# Microcontroller.net
KiCad netlist of a schematic drawn in Altium Designer
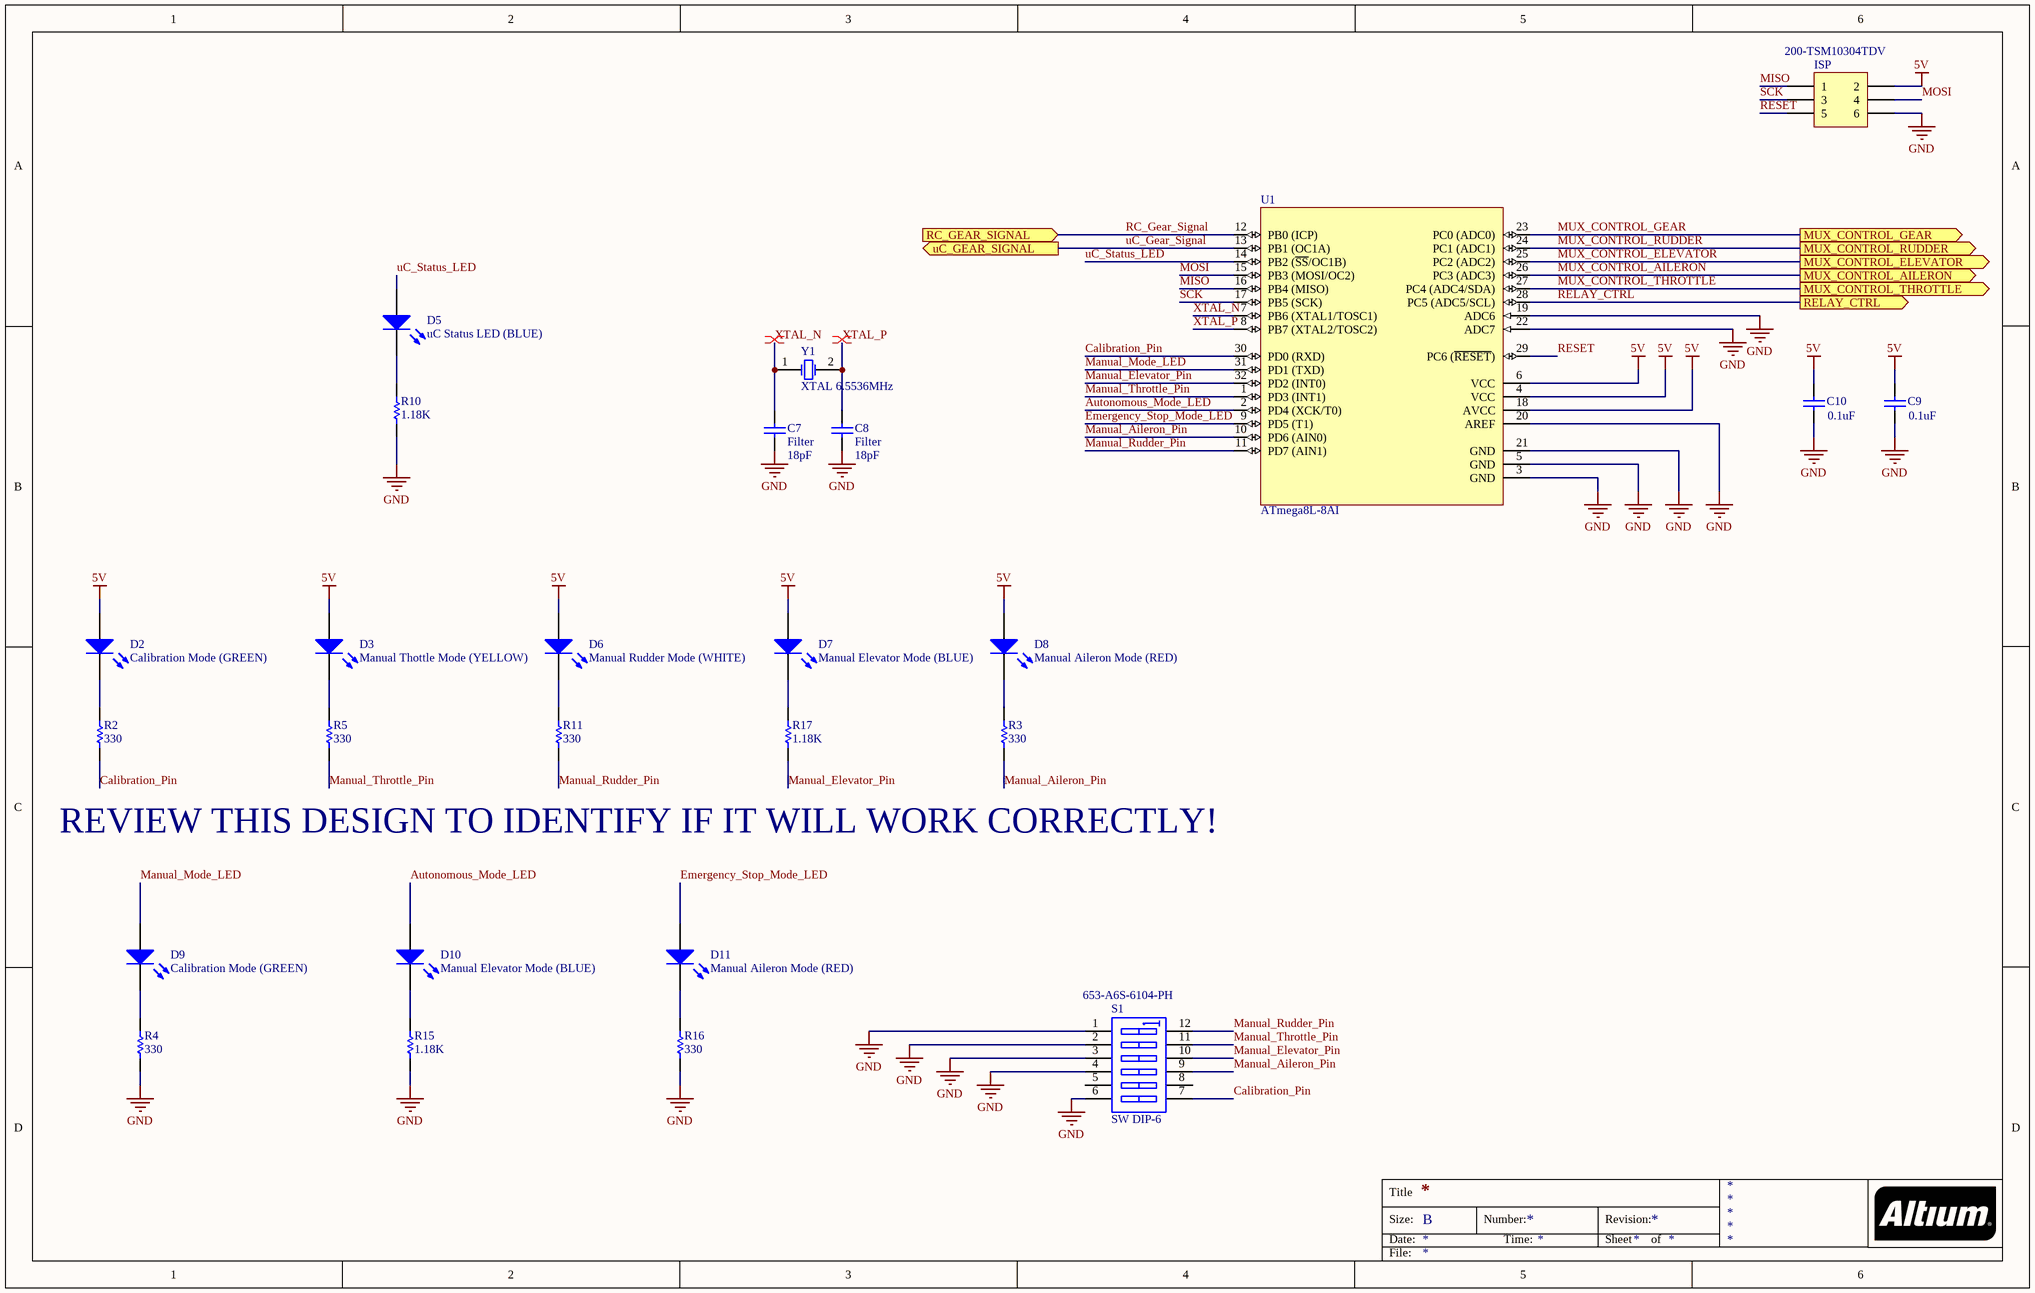
[diagram p0: Microcontroller.SchDoc]

(export (version "E")
  (design (tool "Eeschema 10.0.6"))
  (components
    (comp (ref "C7")
      (value "Filter")
      (footprint "1608[0603]")
      (description "Capacitor")
      (fields
        (field (name "ALTIUM_VALUE") "18pF")
        (field (name "MANUFACTURER") "KEMET")
        (field (name "TOLERANCE") "1%")
        (field (name "PUBLISHER") "Altium Limited")
      )
      (libsource (lib "Miscellaneous Devices") (part "Cap"))
    )
    (comp (ref "C8")
      (value "Filter")
      (footprint "1608[0603]")
      (description "Capacitor")
      (fields
        (field (name "ALTIUM_VALUE") "18pF")
        (field (name "MANUFACTURER") "KEMET")
        (field (name "TOLERANCE") "1%")
        (field (name "PUBLISHER") "Altium Limited")
      )
      (libsource (lib "Miscellaneous Devices") (part "Cap"))
    )
    (comp (ref "C9")
      (value "0.1uF")
      (footprint "1608[0603]")
      (description "Multilayer Ceramic Capacitors MLCC - SMD/SMT 0603 .1uF 50volts X7R 10%")
      (fields
        (field (name "MANUFACTURER PART NUMBER") "VJ0603Y104KXAAC")
        (field (name "MANUFACTURER") "Vishay Semiconductors")
      )
      (libsource (lib "Miscellaneous Devices") (part "Cap"))
    )
    (comp (ref "C10")
      (value "0.1uF")
      (footprint "1608[0603]")
      (description "Multilayer Ceramic Capacitors MLCC - SMD/SMT 0603 .1uF 50volts X7R 10%")
      (fields
        (field (name "MANUFACTURER PART NUMBER") "VJ0603Y104KXAAC")
        (field (name "MANUFACTURER") "Vishay Semiconductors")
      )
      (libsource (lib "Miscellaneous Devices") (part "Cap"))
    )
    (comp (ref "D2")
      (value "Calibration Mode (GREEN)")
      (footprint "1608[0603]")
      (description "Standard LEDs - SMD Ultra Green, 574nm 2.2V, 45mcd")
      (fields
        (field (name "MANUFACTURER") "Lumex")
        (field (name "MANUFACTURER PART NUMBER") "SML-LX0603SUGW-TR")
      )
      (libsource (lib "Miscellaneous Devices") (part "LED0"))
    )
    (comp (ref "D3")
      (value "Manual Thottle Mode (YELLOW)")
      (footprint "1608[0603]")
      (description "Standard LEDs - SMD Yellow 589nm 22mcd 5mA")
      (fields
        (field (name "MANUFACTURER PART NUMBER") "LTST-C193KSKT-5A")
        (field (name "MANUFACTURER") "Vishay Lite-On")
      )
      (libsource (lib "Miscellaneous Devices") (part "LED0"))
    )
    (comp (ref "D5")
      (value "uC Status LED (BLUE)")
      (footprint "1608[0603]")
      (description "Standard LEDs - SMD 0603 Dome Lens LED Blue- 470nm")
      (fields
        (field (name "MANUFACTURER PART NUMBER") "APHD1608LVBC/D")
        (field (name "MANUFACTURER") "Kingbright")
      )
      (libsource (lib "Miscellaneous Devices") (part "LED0"))
    )
    (comp (ref "D6")
      (value "Manual Rudder Mode (WHITE)")
      (footprint "1608[0603]")
      (description "Standard LEDs - SMD CHIPLED, WHITE")
      (fields
        (field (name "MANUFACTURER") "Osram Opto")
        (field (name "MANUFACTURER PART NUMBER") "Q65110-A7209")
      )
      (libsource (lib "Miscellaneous Devices") (part "LED0"))
    )
    (comp (ref "D7")
      (value "Manual Elevator Mode (BLUE)")
      (footprint "1608[0603]")
      (description "Standard LEDs - SMD 0603 Dome Lens LED Blue- 470nm")
      (fields
        (field (name "MANUFACTURER PART NUMBER") "APHD1608LVBC/D")
        (field (name "MANUFACTURER") "Kingbright")
      )
      (libsource (lib "Miscellaneous Devices") (part "LED0"))
    )
    (comp (ref "D8")
      (value "Manual Aileron Mode (RED)")
      (footprint "1608[0603]")
      (description "Standard LEDs - SMD Super Red, 660nm 1.7V, 45mcd")
      (fields
        (field (name "MANUFACTURER PART NUMBER") "SML-LX0603SRW-TR")
        (field (name "MANUFACTURER") "Lumex")
      )
      (libsource (lib "Miscellaneous Devices") (part "LED0"))
    )
    (comp (ref "D9")
      (value "Calibration Mode (GREEN)")
      (footprint "1608[0603]")
      (description "Standard LEDs - SMD Ultra Green, 574nm 2.2V, 45mcd")
      (fields
        (field (name "MANUFACTURER") "Lumex")
        (field (name "MANUFACTURER PART NUMBER") "SML-LX0603SUGW-TR")
      )
      (libsource (lib "Miscellaneous Devices") (part "LED0"))
    )
    (comp (ref "D10")
      (value "Manual Elevator Mode (BLUE)")
      (footprint "1608[0603]")
      (description "Standard LEDs - SMD 0603 Dome Lens LED Blue- 470nm")
      (fields
        (field (name "MANUFACTURER PART NUMBER") "APHD1608LVBC/D")
        (field (name "MANUFACTURER") "Kingbright")
      )
      (libsource (lib "Miscellaneous Devices") (part "LED0"))
    )
    (comp (ref "D11")
      (value "Manual Aileron Mode (RED)")
      (footprint "1608[0603]")
      (description "Standard LEDs - SMD Super Red, 660nm 1.7V, 45mcd")
      (fields
        (field (name "MANUFACTURER PART NUMBER") "SML-LX0603SRW-TR")
        (field (name "MANUFACTURER") "Lumex")
      )
      (libsource (lib "Miscellaneous Devices") (part "LED0"))
    )
    (comp (ref "ISP")
      (value "Header 3X2")
      (footprint "HDR2X3")
      (description "Header, 3-Pin, Dual row")
      (fields
        (field (name "SUPPLIER PART NUMBER 1") "200-TSM10304TDV")
        (field (name "MANUFACTURER") "Samtec")
        (field (name "MANUFACTURER PART NUMBER") "TSM-103-04-T-DV")
        (field (name "PUBLISHER") "Altium Limited")
      )
      (libsource (lib "Miscellaneous Connectors") (part "Header 3X2"))
    )
    (comp (ref "R2")
      (value "330")
      (footprint "1608[0603]")
      (description "Thick Film Resistors - SMD 330 ohm 0.5% 0.33W AEC-Q200")
      (fields
        (field (name "MANUFACTURER") "KOA Speer")
        (field (name "MANUFACTURER PART NUMBER") "SG73G1JTTD3300D")
      )
      (libsource (lib "Miscellaneous Devices") (part "Res1"))
    )
    (comp (ref "R3")
      (value "330")
      (footprint "1608[0603]")
      (description "Thick Film Resistors - SMD 330 ohm 0.5% 0.33W AEC-Q200")
      (fields
        (field (name "MANUFACTURER") "KOA Speer")
        (field (name "MANUFACTURER PART NUMBER") "SG73G1JTTD3300D")
      )
      (libsource (lib "Miscellaneous Devices") (part "Res1"))
    )
    (comp (ref "R4")
      (value "330")
      (footprint "1608[0603]")
      (description "Thick Film Resistors - SMD 330 ohm 0.5% 0.33W AEC-Q200")
      (fields
        (field (name "MANUFACTURER") "KOA Speer")
        (field (name "MANUFACTURER PART NUMBER") "SG73G1JTTD3300D")
      )
      (libsource (lib "Miscellaneous Devices") (part "Res1"))
    )
    (comp (ref "R5")
      (value "330")
      (footprint "1608[0603]")
      (description "Thick Film Resistors - SMD 330 ohm 0.5% 0.33W AEC-Q200")
      (fields
        (field (name "MANUFACTURER") "KOA Speer")
        (field (name "MANUFACTURER PART NUMBER") "SG73G1JTTD3300D")
      )
      (libsource (lib "Miscellaneous Devices") (part "Res1"))
    )
    (comp (ref "R10")
      (value "1.18K")
      (footprint "1608[0603]")
      (description "Thin Film Resistors - SMD 1/16W 1.18Kohm 0.5% 25ppm")
      (fields
        (field (name "MANUFACTURER") "Susumu")
        (field (name "MANUFACTURER PART NUMBER") "RR0816P-1181-D-08H")
      )
      (libsource (lib "Miscellaneous Devices") (part "Res1"))
    )
    (comp (ref "R11")
      (value "330")
      (footprint "1608[0603]")
      (description "Thick Film Resistors - SMD 330 ohm 0.5% 0.33W AEC-Q200")
      (fields
        (field (name "MANUFACTURER") "KOA Speer")
        (field (name "MANUFACTURER PART NUMBER") "SG73G1JTTD3300D")
      )
      (libsource (lib "Miscellaneous Devices") (part "Res1"))
    )
    (comp (ref "R15")
      (value "1.18K")
      (footprint "1608[0603]")
      (description "Thin Film Resistors - SMD 1/16W 1.18Kohm 0.5% 25ppm")
      (fields
        (field (name "MANUFACTURER") "Susumu")
        (field (name "MANUFACTURER PART NUMBER") "RR0816P-1181-D-08H")
      )
      (libsource (lib "Miscellaneous Devices") (part "Res1"))
    )
    (comp (ref "R16")
      (value "330")
      (footprint "1608[0603]")
      (description "Thick Film Resistors - SMD 330 ohm 0.5% 0.33W AEC-Q200")
      (fields
        (field (name "MANUFACTURER") "KOA Speer")
        (field (name "MANUFACTURER PART NUMBER") "SG73G1JTTD3300D")
      )
      (libsource (lib "Miscellaneous Devices") (part "Res1"))
    )
    (comp (ref "R17")
      (value "1.18K")
      (footprint "1608[0603]")
      (description "Thin Film Resistors - SMD 1/16W 1.18Kohm 0.5% 25ppm")
      (fields
        (field (name "MANUFACTURER") "Susumu")
        (field (name "MANUFACTURER PART NUMBER") "RR0816P-1181-D-08H")
      )
      (libsource (lib "Miscellaneous Devices") (part "Res1"))
    )
    (comp (ref "S1")
      (value "SW DIP-6")
      (footprint "A6S-6104-H")
      (description "DIP Switches / SIP Switches 6 Pole Raised Act. Dip SW")
      (fields
        (field (name "SUPPLIER PART NUMBER 1") "653-A6S-6104-PH")
        (field (name "MANUFACTURER PART NUMBER") "A6S-6104-PH")
        (field (name "MANUFACTURER") "Omron")
      )
      (libsource (lib "Miscellaneous Devices") (part "SW DIP-6"))
    )
    (comp (ref "U1")
      (value "ATmega8L-8AI")
      (footprint "32A_N")
      (description "8-Bit AVR Microcontroller with 8K Bytes of In-System Programmable Flash Memory")
      (fields (field (name "PUBLISHER") "Altium Limited"))
      (libsource (lib "Atmel Microcontroller 8-Bit AVR") (part "ATmega8L-8AI"))
    )
    (comp (ref "Y1")
      (value "XTAL 6.5536MHz")
      (footprint "HC49/4H_SMX")
      (description "Crystals 6.5536MHz SERIES")
      (fields
        (field (name "MANUFACTURER") "ECS International")
        (field (name "MANUFACTURER PART NUMBER") "ECS-65.5-S-5PX-TR")
      )
      (libsource (lib "Miscellaneous Devices") (part "XTAL"))
    )
  )
  (nets
    (net (code "1") (name "/Autonomous_Mode_LED") (class "Default")
      (node (ref "D10") (pin "1") (pinfunction "A_1") (pintype "passive"))
      (node (ref "U1") (pin "2") (pinfunction "PD4_(XCK/T0)_2") (pintype "bidirectional"))
    )
    (net (code "2") (name "/Calibration_Pin") (class "Default")
      (node (ref "R2") (pin "1") (pinfunction "1_1") (pintype "passive"))
      (node (ref "S1") (pin "7") (pinfunction "B6_7") (pintype "passive"))
      (node (ref "U1") (pin "30") (pinfunction "PD0_(RXD)_30") (pintype "bidirectional"))
    )
    (net (code "3") (name "/Emergency_Stop_Mode_LED") (class "Default")
      (node (ref "D11") (pin "1") (pinfunction "A_1") (pintype "passive"))
      (node (ref "U1") (pin "9") (pinfunction "PD5_(T1)_9") (pintype "bidirectional"))
    )
    (net (code "4") (name "/MISO") (class "Default")
      (node (ref "ISP") (pin "1") (pinfunction "1_1") (pintype "passive"))
      (node (ref "U1") (pin "16") (pinfunction "PB4_(MISO)_16") (pintype "bidirectional"))
    )
    (net (code "5") (name "/MOSI") (class "Default")
      (node (ref "ISP") (pin "4") (pinfunction "4_4") (pintype "passive"))
      (node (ref "U1") (pin "15") (pinfunction "PB3_(MOSI/OC2)_15") (pintype "bidirectional"))
    )
    (net (code "6") (name "/MUX_CONTROL_AILERON") (class "Default")
      (node (ref "U1") (pin "26") (pinfunction "PC3_(ADC3)_26") (pintype "bidirectional"))
    )
    (net (code "7") (name "/MUX_CONTROL_ELEVATOR") (class "Default")
      (node (ref "U1") (pin "25") (pinfunction "PC2_(ADC2)_25") (pintype "bidirectional"))
    )
    (net (code "8") (name "/MUX_CONTROL_GEAR") (class "Default")
      (node (ref "U1") (pin "23") (pinfunction "PC0_(ADC0)_23") (pintype "bidirectional"))
    )
    (net (code "9") (name "/MUX_CONTROL_RUDDER") (class "Default")
      (node (ref "U1") (pin "24") (pinfunction "PC1_(ADC1)_24") (pintype "bidirectional"))
    )
    (net (code "10") (name "/MUX_CONTROL_THROTTLE") (class "Default")
      (node (ref "U1") (pin "27") (pinfunction "PC4_(ADC4/SDA)_27") (pintype "bidirectional"))
    )
    (net (code "11") (name "/Manual_Aileron_Pin") (class "Default")
      (node (ref "R3") (pin "1") (pinfunction "1_1") (pintype "passive"))
      (node (ref "S1") (pin "9") (pinfunction "B4_9") (pintype "passive"))
      (node (ref "U1") (pin "10") (pinfunction "PD6_(AIN0)_10") (pintype "bidirectional"))
    )
    (net (code "12") (name "/Manual_Elevator_Pin") (class "Default")
      (node (ref "R17") (pin "1") (pinfunction "1_1") (pintype "passive"))
      (node (ref "S1") (pin "10") (pinfunction "B3_10") (pintype "passive"))
      (node (ref "U1") (pin "32") (pinfunction "PD2_(INT0)_32") (pintype "bidirectional"))
    )
    (net (code "13") (name "/Manual_Mode_LED") (class "Default")
      (node (ref "D9") (pin "1") (pinfunction "A_1") (pintype "passive"))
      (node (ref "U1") (pin "31") (pinfunction "PD1_(TXD)_31") (pintype "bidirectional"))
    )
    (net (code "14") (name "/Manual_Rudder_Pin") (class "Default")
      (node (ref "R11") (pin "1") (pinfunction "1_1") (pintype "passive"))
      (node (ref "S1") (pin "12") (pinfunction "B1_12") (pintype "passive"))
      (node (ref "U1") (pin "11") (pinfunction "PD7_(AIN1)_11") (pintype "bidirectional"))
    )
    (net (code "15") (name "/Manual_Throttle_Pin") (class "Default")
      (node (ref "R5") (pin "1") (pinfunction "1_1") (pintype "passive"))
      (node (ref "S1") (pin "11") (pinfunction "B2_11") (pintype "passive"))
      (node (ref "U1") (pin "1") (pinfunction "PD3_(INT1)_1") (pintype "bidirectional"))
    )
    (net (code "16") (name "/RC_Gear_Signal") (class "Default")
      (node (ref "U1") (pin "12") (pinfunction "PB0_(ICP)_12") (pintype "bidirectional"))
    )
    (net (code "17") (name "/RELAY_CTRL") (class "Default")
      (node (ref "U1") (pin "28") (pinfunction "PC5_(ADC5/SCL)_28") (pintype "bidirectional"))
    )
    (net (code "18") (name "/RESET") (class "Default")
      (node (ref "ISP") (pin "5") (pinfunction "5_5") (pintype "passive"))
      (node (ref "U1") (pin "29") (pinfunction "PC6_(~{RESET})_29") (pintype "bidirectional"))
    )
    (net (code "19") (name "/SCK") (class "Default")
      (node (ref "ISP") (pin "3") (pinfunction "3_3") (pintype "passive"))
      (node (ref "U1") (pin "17") (pinfunction "PB5_(SCK)_17") (pintype "bidirectional"))
    )
    (net (code "20") (name "/XTAL_N") (class "Default")
      (node (ref "C7") (pin "2") (pinfunction "2_2") (pintype "passive"))
      (node (ref "U1") (pin "7") (pinfunction "PB6_(XTAL1/TOSC1)_7") (pintype "bidirectional"))
      (node (ref "Y1") (pin "1") (pinfunction "OSC1_1") (pintype "passive"))
    )
    (net (code "21") (name "/XTAL_P") (class "Default")
      (node (ref "C8") (pin "2") (pinfunction "2_2") (pintype "passive"))
      (node (ref "U1") (pin "8") (pinfunction "PB7_(XTAL2/TOSC2)_8") (pintype "bidirectional"))
      (node (ref "Y1") (pin "2") (pinfunction "OSC2_2") (pintype "passive"))
    )
    (net (code "22") (name "/uC_Gear_Signal") (class "Default")
      (node (ref "U1") (pin "13") (pinfunction "PB1_(OC1A)_13") (pintype "bidirectional"))
    )
    (net (code "23") (name "/uC_Status_LED") (class "Default")
      (node (ref "D5") (pin "1") (pinfunction "A_1") (pintype "passive"))
      (node (ref "U1") (pin "14") (pinfunction "PB2_(~{SS}/OC1B)_14") (pintype "bidirectional"))
    )
    (net (code "24") (name "5V") (class "Default")
      (node (ref "C10") (pin "1") (pinfunction "1_1") (pintype "passive"))
      (node (ref "C9") (pin "1") (pinfunction "1_1") (pintype "passive"))
      (node (ref "D2") (pin "1") (pinfunction "A_1") (pintype "passive"))
      (node (ref "D3") (pin "1") (pinfunction "A_1") (pintype "passive"))
      (node (ref "D6") (pin "1") (pinfunction "A_1") (pintype "passive"))
      (node (ref "D7") (pin "1") (pinfunction "A_1") (pintype "passive"))
      (node (ref "D8") (pin "1") (pinfunction "A_1") (pintype "passive"))
      (node (ref "ISP") (pin "2") (pinfunction "2_2") (pintype "passive"))
      (node (ref "U1") (pin "18") (pinfunction "AVCC_18") (pintype "power_in"))
      (node (ref "U1") (pin "4") (pinfunction "VCC_4") (pintype "power_in"))
      (node (ref "U1") (pin "6") (pinfunction "VCC_6") (pintype "power_in"))
    )
    (net (code "25") (name "GND") (class "Default")
      (node (ref "C10") (pin "2") (pinfunction "2_2") (pintype "passive"))
      (node (ref "C7") (pin "1") (pinfunction "1_1") (pintype "passive"))
      (node (ref "C8") (pin "1") (pinfunction "1_1") (pintype "passive"))
      (node (ref "C9") (pin "2") (pinfunction "2_2") (pintype "passive"))
      (node (ref "ISP") (pin "6") (pinfunction "6_6") (pintype "passive"))
      (node (ref "R10") (pin "1") (pinfunction "1_1") (pintype "passive"))
      (node (ref "R15") (pin "1") (pinfunction "1_1") (pintype "passive"))
      (node (ref "R16") (pin "1") (pinfunction "1_1") (pintype "passive"))
      (node (ref "R4") (pin "1") (pinfunction "1_1") (pintype "passive"))
      (node (ref "S1") (pin "1") (pinfunction "A1_1") (pintype "passive"))
      (node (ref "S1") (pin "2") (pinfunction "A2_2") (pintype "passive"))
      (node (ref "S1") (pin "3") (pinfunction "A3_3") (pintype "passive"))
      (node (ref "S1") (pin "4") (pinfunction "A4_4") (pintype "passive"))
      (node (ref "S1") (pin "6") (pinfunction "A6_6") (pintype "passive"))
      (node (ref "U1") (pin "19") (pinfunction "ADC6_19") (pintype "input"))
      (node (ref "U1") (pin "20") (pinfunction "AREF_20") (pintype "passive"))
      (node (ref "U1") (pin "21") (pinfunction "GND_21") (pintype "power_in"))
      (node (ref "U1") (pin "22") (pinfunction "ADC7_22") (pintype "input"))
      (node (ref "U1") (pin "3") (pinfunction "GND_3") (pintype "power_in"))
      (node (ref "U1") (pin "5") (pinfunction "GND_5") (pintype "power_in"))
    )
    (net (code "26") (name "Net-(D2-K)") (class "Default")
      (node (ref "D2") (pin "2") (pinfunction "K_2") (pintype "passive"))
      (node (ref "R2") (pin "2") (pinfunction "2_2") (pintype "passive"))
    )
    (net (code "27") (name "Net-(D3-K)") (class "Default")
      (node (ref "D3") (pin "2") (pinfunction "K_2") (pintype "passive"))
      (node (ref "R5") (pin "2") (pinfunction "2_2") (pintype "passive"))
    )
    (net (code "28") (name "Net-(D5-K)") (class "Default")
      (node (ref "D5") (pin "2") (pinfunction "K_2") (pintype "passive"))
      (node (ref "R10") (pin "2") (pinfunction "2_2") (pintype "passive"))
    )
    (net (code "29") (name "Net-(D6-K)") (class "Default")
      (node (ref "D6") (pin "2") (pinfunction "K_2") (pintype "passive"))
      (node (ref "R11") (pin "2") (pinfunction "2_2") (pintype "passive"))
    )
    (net (code "30") (name "Net-(D7-K)") (class "Default")
      (node (ref "D7") (pin "2") (pinfunction "K_2") (pintype "passive"))
      (node (ref "R17") (pin "2") (pinfunction "2_2") (pintype "passive"))
    )
    (net (code "31") (name "Net-(D8-K)") (class "Default")
      (node (ref "D8") (pin "2") (pinfunction "K_2") (pintype "passive"))
      (node (ref "R3") (pin "2") (pinfunction "2_2") (pintype "passive"))
    )
    (net (code "32") (name "Net-(D9-K)") (class "Default")
      (node (ref "D9") (pin "2") (pinfunction "K_2") (pintype "passive"))
      (node (ref "R4") (pin "2") (pinfunction "2_2") (pintype "passive"))
    )
    (net (code "33") (name "Net-(D10-K)") (class "Default")
      (node (ref "D10") (pin "2") (pinfunction "K_2") (pintype "passive"))
      (node (ref "R15") (pin "2") (pinfunction "2_2") (pintype "passive"))
    )
    (net (code "34") (name "Net-(D11-K)") (class "Default")
      (node (ref "D11") (pin "2") (pinfunction "K_2") (pintype "passive"))
      (node (ref "R16") (pin "2") (pinfunction "2_2") (pintype "passive"))
    )
    (net (code "35") (name "unconnected-(S1-A5-Pad5)") (class "Default")
      (node (ref "S1") (pin "5") (pinfunction "A5_5") (pintype "passive"))
    )
    (net (code "36") (name "unconnected-(S1-B5-Pad8)") (class "Default")
      (node (ref "S1") (pin "8") (pinfunction "B5_8") (pintype "passive"))
    )
  )
)
